# Current_Voltage_Sensors.net
KiCad netlist of a schematic drawn in Altium Designer
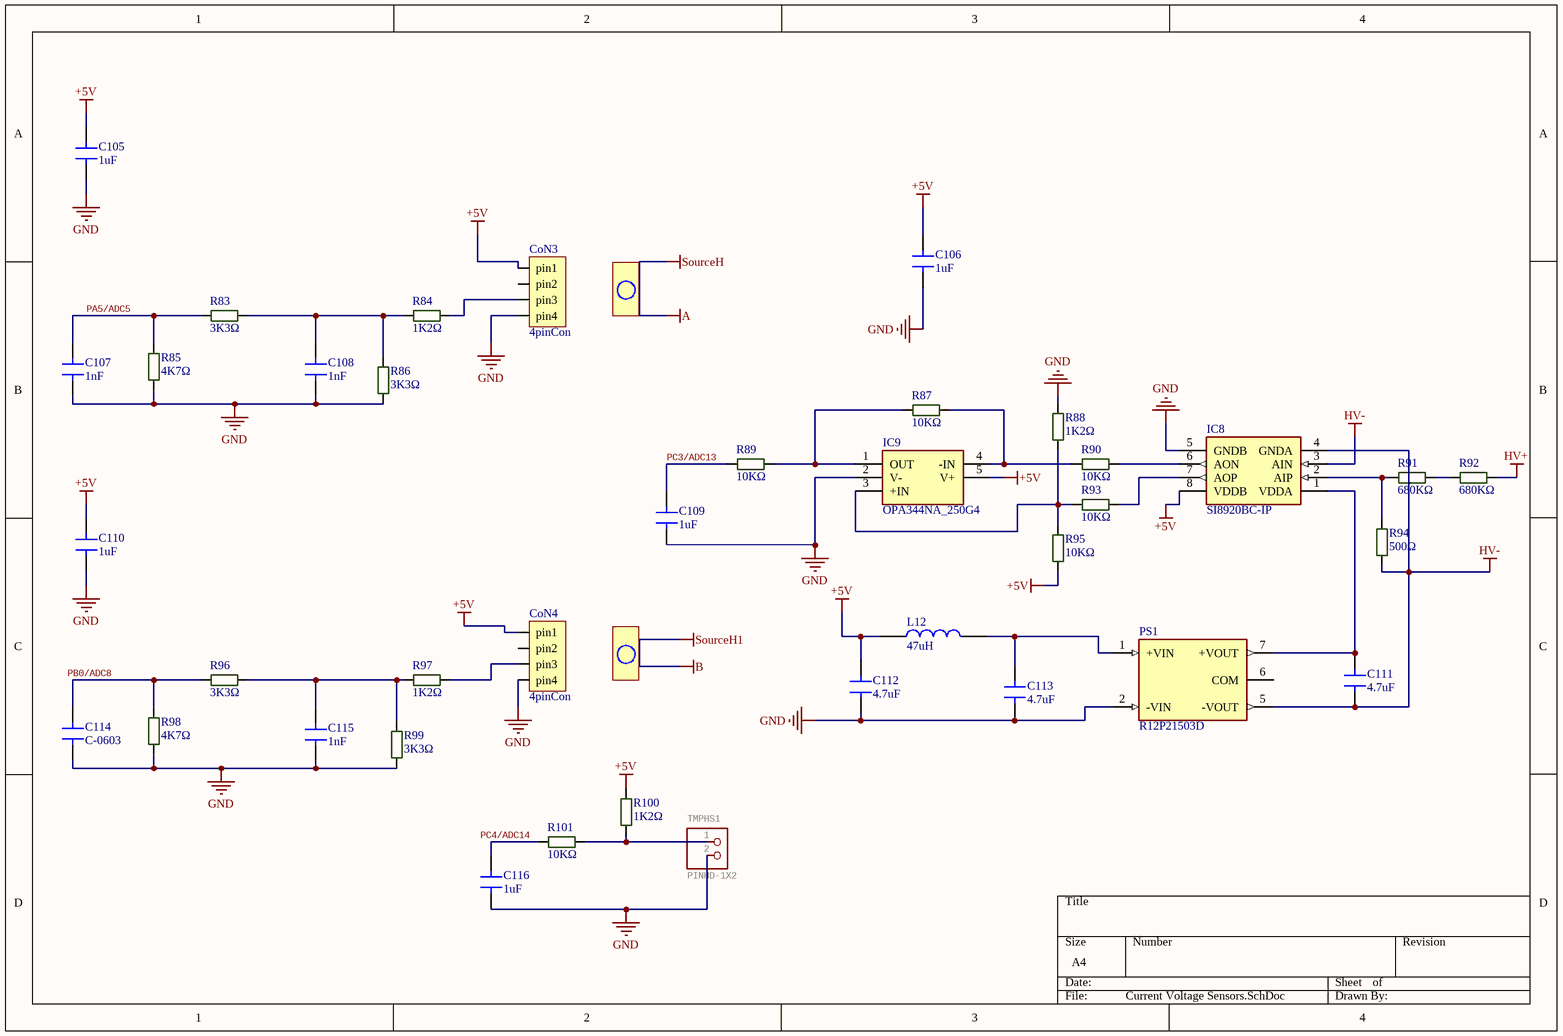
[diagram p0: Current Voltage Sensors.SchDoc]

(export (version "E")
  (design (tool "Eeschema 10.0.6"))
  (components
    (comp (ref "*1")
      (value "current transducer")
      (footprint "currenttransducer")
      (libsource (lib "Gate Driver Board") (part "current transducer"))
    )
    (comp (ref "*2")
      (value "current transducer")
      (footprint "currenttransducer")
      (libsource (lib "Gate Driver Board") (part "current transducer"))
    )
    (comp (ref "C105")
      (value "1uF")
      (footprint "C-0603W")
      (libsource (lib "Gate Driver Board") (part "C-0603"))
    )
    (comp (ref "C106")
      (value "1uF")
      (footprint "C-0805")
      (libsource (lib "Gate Driver Board") (part "C-0805"))
    )
    (comp (ref "C107")
      (value "1nF")
      (footprint "C-0603W")
      (libsource (lib "Gate Driver Board") (part "C-0603"))
    )
    (comp (ref "C108")
      (value "1nF")
      (footprint "C-0603W")
      (libsource (lib "Gate Driver Board") (part "C-0603"))
    )
    (comp (ref "C109")
      (value "1uF")
      (footprint "C-0805")
      (libsource (lib "Gate Driver Board") (part "C-0805"))
    )
    (comp (ref "C110")
      (value "1uF")
      (footprint "C-0603W")
      (libsource (lib "Gate Driver Board") (part "C-0603"))
    )
    (comp (ref "C111")
      (value "4.7uF")
      (footprint "C-1206")
      (libsource (lib "Gate Driver Board") (part "C-1206"))
    )
    (comp (ref "C112")
      (value "4.7uF")
      (footprint "C-1206")
      (description "Cap1206 4.7uF")
      (fields (field (name "ÖZDISAN PART NUMBER") "CL31B475KBHNNNE") (field (name "MANUFACTURER") "SAMSUNG"))
      (libsource (lib "Gate Driver Board") (part "Cap1206"))
    )
    (comp (ref "C113")
      (value "4.7uF")
      (footprint "C-1206")
      (description "Cap1206 4.7uF")
      (fields (field (name "ÖZDISAN PART NUMBER") "CL31B475KBHNNNE") (field (name "MANUFACTURER") "SAMSUNG"))
      (libsource (lib "Gate Driver Board") (part "Cap1206"))
    )
    (comp (ref "C114")
      (value "C-0603")
      (footprint "C-0603W")
      (libsource (lib "Gate Driver Board") (part "C-0603"))
    )
    (comp (ref "C115")
      (value "1nF")
      (footprint "C-0603W")
      (libsource (lib "Gate Driver Board") (part "C-0603"))
    )
    (comp (ref "C116")
      (value "1uF")
      (footprint "C-0805")
      (libsource (lib "Gate Driver Board") (part "C-0805"))
    )
    (comp (ref "CoN3")
      (value "4pinCon")
      (footprint "4pinCon")
      (libsource (lib "Gate Driver Board") (part "4pinCon"))
    )
    (comp (ref "CoN4")
      (value "4pinCon")
      (footprint "4pinCon")
      (libsource (lib "Gate Driver Board") (part "4pinCon"))
    )
    (comp (ref "IC8")
      (value "SI8920BC-IP")
      (footprint "SamacSys:SOP254P965X419-8N")
      (description "Integrated Circuit")
      (fields (field (name "MOUSER PART NUMBER") "634-SI8920BC-IP"))
      (libsource (lib "*") (part "SI8920BC-IP"))
    )
    (comp (ref "IC9")
      (value "OPA344NA_250G4")
      (footprint "SamacSys:SOT95P280X145-5N")
      (description "Integrated Circuit")
      (fields
        (field (name "MANUFACTURER_PART_NUMBER") "OPA344NA/250G4")
        (field (name "MOUSER PART NUMBER") "595-OPA344NA/250G4")
      )
      (libsource (lib "*") (part "OPA344NA_250G4"))
    )
    (comp (ref "L12")
      (value "47uH")
      (footprint "WE-TPC_282892")
      (libsource (lib "Gate Driver Board") (part "inductor"))
    )
    (comp (ref "PS1")
      (value "R12P21503D")
      (footprint "CONV_R12P21503D")
      (description "2W DC/DC-Converter 'ECONOLINE' SIP7 6.4kV unreg")
      (fields (field (name "MF") "Recom Power") (field (name "DIGI-KEY_PART_NUMBER") "945-3069-5-ND"))
      (libsource (lib "Gate Driver Board") (part "R12P21503D"))
    )
    (comp (ref "R83")
      (value "3K3Ω")
      (footprint "R-0603R")
      (libsource (lib "Gate Driver Board") (part "R-0603"))
    )
    (comp (ref "R84")
      (value "1K2Ω")
      (footprint "R-0603R")
      (libsource (lib "Gate Driver Board") (part "R-0603"))
    )
    (comp (ref "R85")
      (value "4K7Ω")
      (footprint "R-0603R")
      (libsource (lib "Gate Driver Board") (part "R-0603"))
    )
    (comp (ref "R86")
      (value "3K3Ω")
      (footprint "R-0603R")
      (libsource (lib "Gate Driver Board") (part "R-0603"))
    )
    (comp (ref "R87")
      (value "10KΩ")
      (footprint "R-0805")
      (libsource (lib "Gate Driver Board") (part "R-0805"))
    )
    (comp (ref "R88")
      (value "1K2Ω")
      (footprint "R-0805")
      (libsource (lib "Gate Driver Board") (part "R-0805"))
    )
    (comp (ref "R89")
      (value "10KΩ")
      (footprint "R-0805")
      (libsource (lib "Gate Driver Board") (part "R-0805"))
    )
    (comp (ref "R90")
      (value "10KΩ")
      (footprint "R-0805")
      (libsource (lib "Gate Driver Board") (part "R-0805"))
    )
    (comp (ref "R91")
      (value "680KΩ")
      (footprint "R-1206")
      (description "Res1206")
      (libsource (lib "Gate Driver Board") (part "R-1206"))
    )
    (comp (ref "R92")
      (value "680KΩ")
      (footprint "R-1206")
      (description "Res1206")
      (libsource (lib "Gate Driver Board") (part "R-1206"))
    )
    (comp (ref "R93")
      (value "10KΩ")
      (footprint "R-0805")
      (libsource (lib "Gate Driver Board") (part "R-0805"))
    )
    (comp (ref "R94")
      (value "500Ω")
      (footprint "R-1206")
      (description "Res1206")
      (libsource (lib "Gate Driver Board") (part "R-1206"))
    )
    (comp (ref "R95")
      (value "10KΩ")
      (footprint "R-0805")
      (libsource (lib "Gate Driver Board") (part "R-0805"))
    )
    (comp (ref "R96")
      (value "3K3Ω")
      (footprint "R-0603R")
      (libsource (lib "Gate Driver Board") (part "R-0603"))
    )
    (comp (ref "R97")
      (value "1K2Ω")
      (footprint "R-0603R")
      (libsource (lib "Gate Driver Board") (part "R-0603"))
    )
    (comp (ref "R98")
      (value "4K7Ω")
      (footprint "R-0603R")
      (libsource (lib "Gate Driver Board") (part "R-0603"))
    )
    (comp (ref "R99")
      (value "3K3Ω")
      (footprint "R-0603R")
      (libsource (lib "Gate Driver Board") (part "R-0603"))
    )
    (comp (ref "R100")
      (value "1K2Ω")
      (footprint "R-0805")
      (libsource (lib "Gate Driver Board") (part "R-0805"))
    )
    (comp (ref "R101")
      (value "10KΩ")
      (footprint "R-0805")
      (libsource (lib "Gate Driver Board") (part "R-0805"))
    )
    (comp (ref "TMPHS1")
      (value "PINHD-1X2")
      (footprint "1X02")
      (description "PIN HEADER")
      (fields (field (name "LIBRARYNAME") "pinhead"))
      (libsource (lib "Gate Driver Board") (part "PINHD-1X2"))
    )
  )
  (nets
    (net (code "1") (name "+5V") (class "Default")
      (node (ref "C105") (pin "2") (pinfunction "2_2") (pintype "passive"))
      (node (ref "C106") (pin "2") (pinfunction "2_2") (pintype "passive"))
      (node (ref "C110") (pin "2") (pinfunction "2_2") (pintype "passive"))
      (node (ref "C112") (pin "2") (pinfunction "2_2") (pintype "passive"))
      (node (ref "CoN3") (pin "1") (pinfunction "pin1_1") (pintype "passive"))
      (node (ref "CoN4") (pin "1") (pinfunction "pin1_1") (pintype "passive"))
      (node (ref "IC8") (pin "8") (pinfunction "VDDB_8") (pintype "power_in"))
      (node (ref "IC9") (pin "5") (pinfunction "V+_5") (pintype "passive"))
      (node (ref "L12") (pin "1") (pinfunction "1_1") (pintype "passive"))
      (node (ref "R100") (pin "1") (pinfunction "1_1") (pintype "passive"))
      (node (ref "R95") (pin "1") (pinfunction "1_1") (pintype "passive"))
    )
    (net (code "2") (name "/PA5{slash}ADC5") (class "Default")
      (node (ref "C107") (pin "2") (pinfunction "2_2") (pintype "passive"))
      (node (ref "R83") (pin "1") (pinfunction "1_1") (pintype "passive"))
      (node (ref "R85") (pin "2") (pinfunction "2_2") (pintype "passive"))
    )
    (net (code "3") (name "/PB0{slash}ADC8") (class "Default")
      (node (ref "C114") (pin "2") (pinfunction "2_2") (pintype "passive"))
      (node (ref "R96") (pin "1") (pinfunction "1_1") (pintype "passive"))
      (node (ref "R98") (pin "2") (pinfunction "2_2") (pintype "passive"))
    )
    (net (code "4") (name "/PC3{slash}ADC13") (class "Default")
      (node (ref "C109") (pin "2") (pinfunction "2_2") (pintype "passive"))
      (node (ref "R89") (pin "2") (pinfunction "2_2") (pintype "passive"))
    )
    (net (code "5") (name "/PC4{slash}ADC14") (class "Default")
      (node (ref "C116") (pin "2") (pinfunction "2_2") (pintype "passive"))
      (node (ref "R101") (pin "2") (pinfunction "2_2") (pintype "passive"))
    )
    (net (code "8") (name "GND") (class "Default")
      (node (ref "C105") (pin "1") (pinfunction "1_1") (pintype "passive"))
      (node (ref "C106") (pin "1") (pinfunction "1_1") (pintype "passive"))
      (node (ref "C107") (pin "1") (pinfunction "1_1") (pintype "passive"))
      (node (ref "C108") (pin "1") (pinfunction "1_1") (pintype "passive"))
      (node (ref "C109") (pin "1") (pinfunction "1_1") (pintype "passive"))
      (node (ref "C110") (pin "1") (pinfunction "1_1") (pintype "passive"))
      (node (ref "C112") (pin "1") (pinfunction "1_1") (pintype "passive"))
      (node (ref "C113") (pin "1") (pinfunction "1_1") (pintype "passive"))
      (node (ref "C114") (pin "1") (pinfunction "1_1") (pintype "passive"))
      (node (ref "C115") (pin "1") (pinfunction "1_1") (pintype "passive"))
      (node (ref "C116") (pin "1") (pinfunction "1_1") (pintype "passive"))
      (node (ref "CoN3") (pin "4") (pinfunction "pin4_4") (pintype "passive"))
      (node (ref "CoN4") (pin "4") (pinfunction "pin4_4") (pintype "passive"))
      (node (ref "IC8") (pin "5") (pinfunction "GNDB_5") (pintype "power_in"))
      (node (ref "IC9") (pin "2") (pinfunction "V-_2") (pintype "passive"))
      (node (ref "PS1") (pin "2") (pinfunction "-VIN_2") (pintype "input"))
      (node (ref "R85") (pin "1") (pinfunction "1_1") (pintype "passive"))
      (node (ref "R86") (pin "1") (pinfunction "1_1") (pintype "passive"))
      (node (ref "R88") (pin "2") (pinfunction "2_2") (pintype "passive"))
      (node (ref "R98") (pin "1") (pinfunction "1_1") (pintype "passive"))
      (node (ref "R99") (pin "1") (pinfunction "1_1") (pintype "passive"))
      (node (ref "TMPHS1") (pin "2") (pinfunction "2_2") (pintype "passive"))
    )
    (net (code "9") (name "HV+") (class "Default")
      (node (ref "R92") (pin "2") (pinfunction "2_2") (pintype "passive"))
    )
    (net (code "10") (name "HV-") (class "Default")
      (node (ref "C111") (pin "1") (pinfunction "1_1") (pintype "passive"))
      (node (ref "IC8") (pin "3") (pinfunction "AIN_3") (pintype "input"))
      (node (ref "IC8") (pin "4") (pinfunction "GNDA_4") (pintype "power_in"))
      (node (ref "PS1") (pin "5") (pinfunction "-VOUT_5") (pintype "output"))
      (node (ref "R94") (pin "1") (pinfunction "1_1") (pintype "passive"))
    )
    (net (code "11") (name "Net-(C108-Pad2)") (class "Default")
      (node (ref "C108") (pin "2") (pinfunction "2_2") (pintype "passive"))
      (node (ref "R83") (pin "2") (pinfunction "2_2") (pintype "passive"))
      (node (ref "R84") (pin "1") (pinfunction "1_1") (pintype "passive"))
      (node (ref "R86") (pin "2") (pinfunction "2_2") (pintype "passive"))
    )
    (net (code "12") (name "Net-(C115-Pad2)") (class "Default")
      (node (ref "C115") (pin "2") (pinfunction "2_2") (pintype "passive"))
      (node (ref "R96") (pin "2") (pinfunction "2_2") (pintype "passive"))
      (node (ref "R97") (pin "1") (pinfunction "1_1") (pintype "passive"))
      (node (ref "R99") (pin "2") (pinfunction "2_2") (pintype "passive"))
    )
    (net (code "13") (name "Net-(CoN3-pin3)") (class "Default")
      (node (ref "CoN3") (pin "3") (pinfunction "pin3_3") (pintype "passive"))
      (node (ref "R84") (pin "2") (pinfunction "2_2") (pintype "passive"))
    )
    (net (code "14") (name "Net-(CoN4-pin3)") (class "Default")
      (node (ref "CoN4") (pin "3") (pinfunction "pin3_3") (pintype "passive"))
      (node (ref "R97") (pin "2") (pinfunction "2_2") (pintype "passive"))
    )
    (net (code "15") (name "Net-(IC8-AIP)") (class "Default")
      (node (ref "IC8") (pin "2") (pinfunction "AIP_2") (pintype "input"))
      (node (ref "R91") (pin "1") (pinfunction "1_1") (pintype "passive"))
      (node (ref "R94") (pin "2") (pinfunction "2_2") (pintype "passive"))
    )
    (net (code "16") (name "Net-(IC8-AON)") (class "Default")
      (node (ref "IC8") (pin "6") (pinfunction "AON_6") (pintype "output"))
      (node (ref "R90") (pin "2") (pinfunction "2_2") (pintype "passive"))
    )
    (net (code "17") (name "Net-(IC8-AOP)") (class "Default")
      (node (ref "IC8") (pin "7") (pinfunction "AOP_7") (pintype "output"))
      (node (ref "R93") (pin "2") (pinfunction "2_2") (pintype "passive"))
    )
    (net (code "18") (name "Net-(IC8-VDDA)") (class "Default")
      (node (ref "C111") (pin "2") (pinfunction "2_2") (pintype "passive"))
      (node (ref "IC8") (pin "1") (pinfunction "VDDA_1") (pintype "power_in"))
      (node (ref "PS1") (pin "7") (pinfunction "+VOUT_7") (pintype "output"))
    )
    (net (code "19") (name "Net-(IC9-+IN)") (class "Default")
      (node (ref "IC9") (pin "3") (pinfunction "+IN_3") (pintype "passive"))
      (node (ref "R88") (pin "1") (pinfunction "1_1") (pintype "passive"))
      (node (ref "R93") (pin "1") (pinfunction "1_1") (pintype "passive"))
      (node (ref "R95") (pin "2") (pinfunction "2_2") (pintype "passive"))
    )
    (net (code "20") (name "Net-(IC9--IN)") (class "Default")
      (node (ref "IC9") (pin "4") (pinfunction "-IN_4") (pintype "passive"))
      (node (ref "R87") (pin "1") (pinfunction "1_1") (pintype "passive"))
      (node (ref "R90") (pin "1") (pinfunction "1_1") (pintype "passive"))
    )
    (net (code "21") (name "Net-(IC9-OUT)") (class "Default")
      (node (ref "IC9") (pin "1") (pinfunction "OUT_1") (pintype "passive"))
      (node (ref "R87") (pin "2") (pinfunction "2_2") (pintype "passive"))
      (node (ref "R89") (pin "1") (pinfunction "1_1") (pintype "passive"))
    )
    (net (code "22") (name "Net-(PS1-+VIN)") (class "Default")
      (node (ref "C113") (pin "2") (pinfunction "2_2") (pintype "passive"))
      (node (ref "L12") (pin "2") (pinfunction "2_2") (pintype "passive"))
      (node (ref "PS1") (pin "1") (pinfunction "+VIN_1") (pintype "input"))
    )
    (net (code "23") (name "Net-(R91-Pad2)") (class "Default")
      (node (ref "R91") (pin "2") (pinfunction "2_2") (pintype "passive"))
      (node (ref "R92") (pin "1") (pinfunction "1_1") (pintype "passive"))
    )
    (net (code "24") (name "Net-(R100-Pad2)") (class "Default")
      (node (ref "R100") (pin "2") (pinfunction "2_2") (pintype "passive"))
      (node (ref "R101") (pin "1") (pinfunction "1_1") (pintype "passive"))
      (node (ref "TMPHS1") (pin "1") (pinfunction "1_1") (pintype "passive"))
    )
    (net (code "25") (name "unconnected-(CoN3-pin2-Pad2)") (class "Default")
      (node (ref "CoN3") (pin "2") (pinfunction "pin2_2") (pintype "passive"))
    )
    (net (code "26") (name "unconnected-(CoN4-pin2-Pad2)") (class "Default")
      (node (ref "CoN4") (pin "2") (pinfunction "pin2_2") (pintype "passive"))
    )
    (net (code "27") (name "unconnected-(PS1-COM-Pad6)") (class "Default")
      (node (ref "PS1") (pin "6") (pinfunction "COM_6") (pintype "power_in"))
    )
  )
)
